# Navspark_NS-T_Adapter.net
KiCad netlist of a schematic drawn in EAGLE
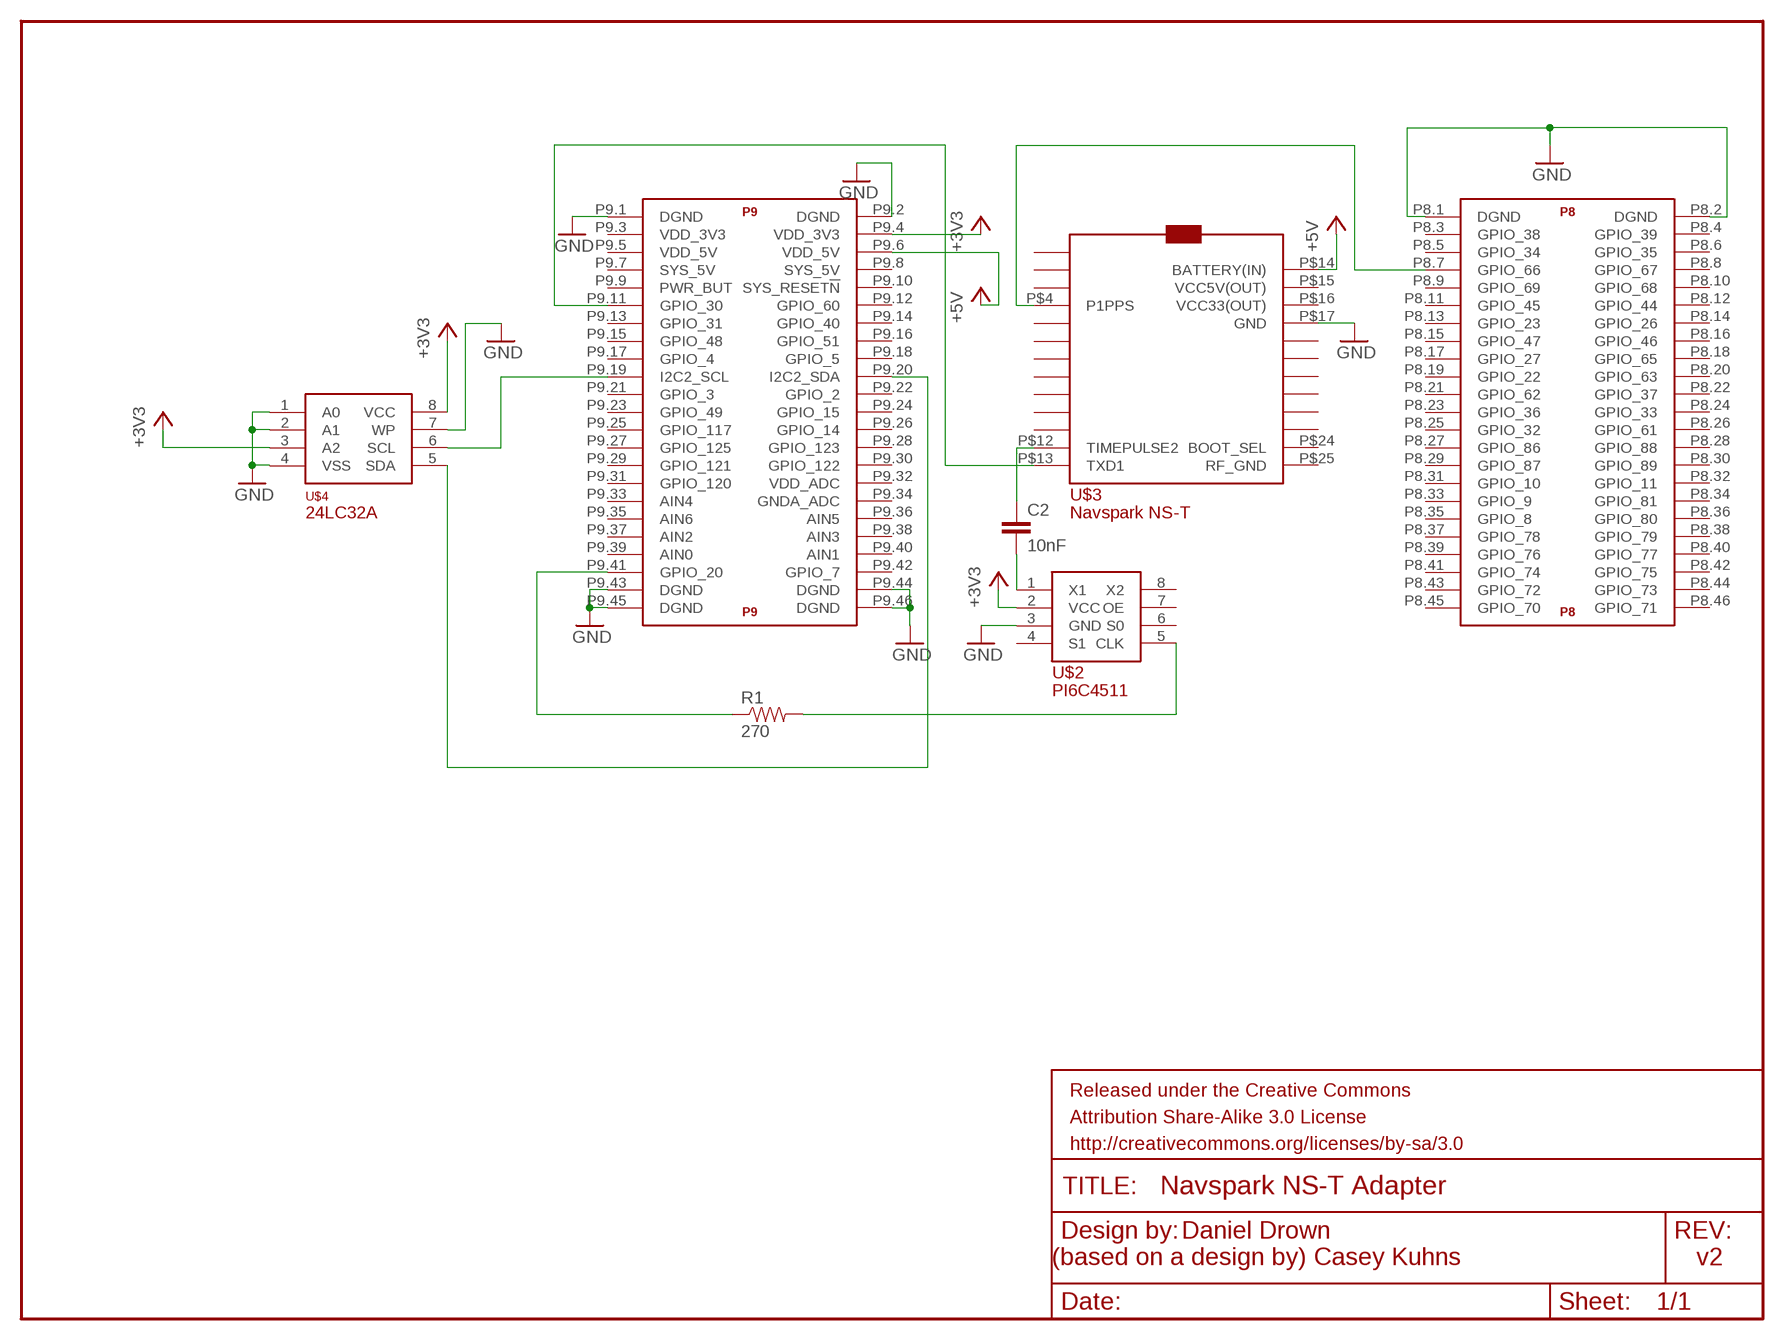
[diagram p0: schematic, sheet 1]

(export (version "E")
  (design (tool "Eeschema 10.0.6"))
  (components
    (comp (ref "C2")
      (value "10nF")
      (footprint "eagle-import:0805")
      (libsource (lib "eagle-import") (part "CAP0805"))
    )
    (comp (ref "FRAME1")
      (value "FRAME-LETTER")
      (footprint "eagle-import:CREATIVE_COMMONS")
      (libsource (lib "eagle-import") (part "FRAME-LETTER"))
    )
    (comp (ref "R1")
      (value "270")
      (footprint "eagle-import:0805")
      (libsource (lib "eagle-import") (part "RESISTOR0805-RES"))
    )
    (comp (ref "U$1")
      (value "BEAGLE_BONE_BLACK_CAPE")
      (footprint "eagle-import:BEAGLE_BONE_BLACK_CAPE")
      (libsource (lib "eagle-import") (part "BEAGLE_BONE_BLACK_CAPE"))
    )
    (comp (ref "U$2")
      (value "PI6C4511WE")
      (footprint "eagle-import:8-SOIC")
      (libsource (lib "eagle-import") (part "PI6C4511WE"))
    )
    (comp (ref "U$3")
      (value "NS-T")
      (footprint "eagle-import:BREADBOARD")
      (libsource (lib "eagle-import") (part "NS-T"))
    )
    (comp (ref "U$4")
      (value "24LC32A")
      (footprint "eagle-import:SOIC8")
      (libsource (lib "eagle-import") (part "24LC32A"))
    )
  )
  (nets
    (net (code "1") (name "+3V3") (class "Default")
      (node (ref "U$1") (pin "P9.4") (pinfunction "VDD_3V3_P9.4") (pintype "bidirectional"))
      (node (ref "U$2") (pin "2") (pinfunction "VCC_2") (pintype "bidirectional"))
      (node (ref "U$4") (pin "3") (pinfunction "A2_3") (pintype "bidirectional"))
      (node (ref "U$4") (pin "8") (pinfunction "VCC_8") (pintype "bidirectional"))
    )
    (net (code "2") (name "+5V") (class "Default")
      (node (ref "U$1") (pin "P9.6") (pinfunction "VDD_5V_P9.6") (pintype "bidirectional"))
      (node (ref "U$3") (pin "P$14") (pinfunction "BATTERY(IN)_P$14") (pintype "power_in"))
    )
    (net (code "3") (name "GND") (class "Default")
      (node (ref "U$1") (pin "P8.1") (pinfunction "DGND_P8.1") (pintype "bidirectional"))
      (node (ref "U$1") (pin "P8.2") (pinfunction "DGND_P8.2") (pintype "bidirectional"))
      (node (ref "U$1") (pin "P9.1") (pinfunction "DGND_P9.1") (pintype "bidirectional"))
      (node (ref "U$1") (pin "P9.2") (pinfunction "DGND_P9.2") (pintype "bidirectional"))
      (node (ref "U$1") (pin "P9.43") (pinfunction "DGND_P9.43") (pintype "bidirectional"))
      (node (ref "U$1") (pin "P9.44") (pinfunction "DGND_P9.44") (pintype "bidirectional"))
      (node (ref "U$1") (pin "P9.45") (pinfunction "DGND_P9.45") (pintype "bidirectional"))
      (node (ref "U$1") (pin "P9.46") (pinfunction "DGND_P9.46") (pintype "bidirectional"))
      (node (ref "U$2") (pin "3") (pinfunction "GND_3") (pintype "bidirectional"))
      (node (ref "U$3") (pin "P$17") (pinfunction "GND_P$17") (pintype "bidirectional"))
      (node (ref "U$4") (pin "1") (pinfunction "A0_1") (pintype "bidirectional"))
      (node (ref "U$4") (pin "2") (pinfunction "A1_2") (pintype "bidirectional"))
      (node (ref "U$4") (pin "4") (pinfunction "VSS_4") (pintype "bidirectional"))
      (node (ref "U$4") (pin "7") (pinfunction "WP_7") (pintype "bidirectional"))
    )
    (net (code "4") (name "Net-(U$1A-GPIO_66)") (class "Default")
      (node (ref "U$1") (pin "P8.7") (pinfunction "GPIO_66_P8.7") (pintype "bidirectional"))
      (node (ref "U$3") (pin "P$4") (pinfunction "P1PPS_P$4") (pintype "output"))
    )
    (net (code "5") (name "Net-(U$1B-GPIO_20)") (class "Default")
      (node (ref "R1") (pin "1") (pinfunction "1_1") (pintype "passive"))
      (node (ref "U$1") (pin "P9.41") (pinfunction "GPIO_20_P9.41") (pintype "bidirectional"))
    )
    (net (code "6") (name "Net-(U$1B-GPIO_30)") (class "Default")
      (node (ref "U$1") (pin "P9.11") (pinfunction "GPIO_30_P9.11") (pintype "bidirectional"))
      (node (ref "U$3") (pin "P$13") (pinfunction "TXD1_P$13") (pintype "output"))
    )
    (net (code "7") (name "Net-(U$1B-I2C2_SCL)") (class "Default")
      (node (ref "U$1") (pin "P9.19") (pinfunction "I2C2_SCL_P9.19") (pintype "bidirectional"))
      (node (ref "U$4") (pin "6") (pinfunction "SCL_6") (pintype "bidirectional"))
    )
    (net (code "8") (name "Net-(U$1B-I2C2_SDA)") (class "Default")
      (node (ref "U$1") (pin "P9.20") (pinfunction "I2C2_SDA_P9.20") (pintype "bidirectional"))
      (node (ref "U$4") (pin "5") (pinfunction "SDA_5") (pintype "bidirectional"))
    )
    (net (code "9") (name "Net-(U$2-CLK)") (class "Default")
      (node (ref "R1") (pin "2") (pinfunction "2_2") (pintype "passive"))
      (node (ref "U$2") (pin "5") (pinfunction "CLK_5") (pintype "bidirectional"))
    )
    (net (code "10") (name "Net-(U$2-X1)") (class "Default")
      (node (ref "C2") (pin "2") (pinfunction "2_2") (pintype "passive"))
      (node (ref "U$2") (pin "1") (pinfunction "X1_1") (pintype "bidirectional"))
    )
    (net (code "11") (name "Net-(U$3-TIMEPULSE2)") (class "Default")
      (node (ref "C2") (pin "1") (pinfunction "1_1") (pintype "passive"))
      (node (ref "U$3") (pin "P$12") (pinfunction "TIMEPULSE2_P$12") (pintype "output"))
    )
    (net (code "12") (name "unconnected-(U$1A-GPIO_8-PadP8.35)") (class "Default")
      (node (ref "U$1") (pin "P8.35") (pinfunction "GPIO_8_P8.35") (pintype "bidirectional"))
    )
    (net (code "13") (name "unconnected-(U$1A-GPIO_9-PadP8.33)") (class "Default")
      (node (ref "U$1") (pin "P8.33") (pinfunction "GPIO_9_P8.33") (pintype "bidirectional"))
    )
    (net (code "14") (name "unconnected-(U$1A-GPIO_10-PadP8.31)") (class "Default")
      (node (ref "U$1") (pin "P8.31") (pinfunction "GPIO_10_P8.31") (pintype "bidirectional"))
    )
    (net (code "15") (name "unconnected-(U$1A-GPIO_11-PadP8.32)") (class "Default")
      (node (ref "U$1") (pin "P8.32") (pinfunction "GPIO_11_P8.32") (pintype "bidirectional"))
    )
    (net (code "16") (name "unconnected-(U$1A-GPIO_22-PadP8.19)") (class "Default")
      (node (ref "U$1") (pin "P8.19") (pinfunction "GPIO_22_P8.19") (pintype "bidirectional"))
    )
    (net (code "17") (name "unconnected-(U$1A-GPIO_23-PadP8.13)") (class "Default")
      (node (ref "U$1") (pin "P8.13") (pinfunction "GPIO_23_P8.13") (pintype "bidirectional"))
    )
    (net (code "18") (name "unconnected-(U$1A-GPIO_26-PadP8.14)") (class "Default")
      (node (ref "U$1") (pin "P8.14") (pinfunction "GPIO_26_P8.14") (pintype "bidirectional"))
    )
    (net (code "19") (name "unconnected-(U$1A-GPIO_27-PadP8.17)") (class "Default")
      (node (ref "U$1") (pin "P8.17") (pinfunction "GPIO_27_P8.17") (pintype "bidirectional"))
    )
    (net (code "20") (name "unconnected-(U$1A-GPIO_32-PadP8.25)") (class "Default")
      (node (ref "U$1") (pin "P8.25") (pinfunction "GPIO_32_P8.25") (pintype "bidirectional"))
    )
    (net (code "21") (name "unconnected-(U$1A-GPIO_33-PadP8.24)") (class "Default")
      (node (ref "U$1") (pin "P8.24") (pinfunction "GPIO_33_P8.24") (pintype "bidirectional"))
    )
    (net (code "22") (name "unconnected-(U$1A-GPIO_34-PadP8.5)") (class "Default")
      (node (ref "U$1") (pin "P8.5") (pinfunction "GPIO_34_P8.5") (pintype "bidirectional"))
    )
    (net (code "23") (name "unconnected-(U$1A-GPIO_35-PadP8.6)") (class "Default")
      (node (ref "U$1") (pin "P8.6") (pinfunction "GPIO_35_P8.6") (pintype "bidirectional"))
    )
    (net (code "24") (name "unconnected-(U$1A-GPIO_36-PadP8.23)") (class "Default")
      (node (ref "U$1") (pin "P8.23") (pinfunction "GPIO_36_P8.23") (pintype "bidirectional"))
    )
    (net (code "25") (name "unconnected-(U$1A-GPIO_37-PadP8.22)") (class "Default")
      (node (ref "U$1") (pin "P8.22") (pinfunction "GPIO_37_P8.22") (pintype "bidirectional"))
    )
    (net (code "26") (name "unconnected-(U$1A-GPIO_38-PadP8.3)") (class "Default")
      (node (ref "U$1") (pin "P8.3") (pinfunction "GPIO_38_P8.3") (pintype "bidirectional"))
    )
    (net (code "27") (name "unconnected-(U$1A-GPIO_39-PadP8.4)") (class "Default")
      (node (ref "U$1") (pin "P8.4") (pinfunction "GPIO_39_P8.4") (pintype "bidirectional"))
    )
    (net (code "28") (name "unconnected-(U$1A-GPIO_44-PadP8.12)") (class "Default")
      (node (ref "U$1") (pin "P8.12") (pinfunction "GPIO_44_P8.12") (pintype "bidirectional"))
    )
    (net (code "29") (name "unconnected-(U$1A-GPIO_45-PadP8.11)") (class "Default")
      (node (ref "U$1") (pin "P8.11") (pinfunction "GPIO_45_P8.11") (pintype "bidirectional"))
    )
    (net (code "30") (name "unconnected-(U$1A-GPIO_46-PadP8.16)") (class "Default")
      (node (ref "U$1") (pin "P8.16") (pinfunction "GPIO_46_P8.16") (pintype "bidirectional"))
    )
    (net (code "31") (name "unconnected-(U$1A-GPIO_47-PadP8.15)") (class "Default")
      (node (ref "U$1") (pin "P8.15") (pinfunction "GPIO_47_P8.15") (pintype "bidirectional"))
    )
    (net (code "32") (name "unconnected-(U$1A-GPIO_61-PadP8.26)") (class "Default")
      (node (ref "U$1") (pin "P8.26") (pinfunction "GPIO_61_P8.26") (pintype "bidirectional"))
    )
    (net (code "33") (name "unconnected-(U$1A-GPIO_62-PadP8.21)") (class "Default")
      (node (ref "U$1") (pin "P8.21") (pinfunction "GPIO_62_P8.21") (pintype "bidirectional"))
    )
    (net (code "34") (name "unconnected-(U$1A-GPIO_63-PadP8.20)") (class "Default")
      (node (ref "U$1") (pin "P8.20") (pinfunction "GPIO_63_P8.20") (pintype "bidirectional"))
    )
    (net (code "35") (name "unconnected-(U$1A-GPIO_65-PadP8.18)") (class "Default")
      (node (ref "U$1") (pin "P8.18") (pinfunction "GPIO_65_P8.18") (pintype "bidirectional"))
    )
    (net (code "36") (name "unconnected-(U$1A-GPIO_67-PadP8.8)") (class "Default")
      (node (ref "U$1") (pin "P8.8") (pinfunction "GPIO_67_P8.8") (pintype "bidirectional"))
    )
    (net (code "37") (name "unconnected-(U$1A-GPIO_68-PadP8.10)") (class "Default")
      (node (ref "U$1") (pin "P8.10") (pinfunction "GPIO_68_P8.10") (pintype "bidirectional"))
    )
    (net (code "38") (name "unconnected-(U$1A-GPIO_69-PadP8.9)") (class "Default")
      (node (ref "U$1") (pin "P8.9") (pinfunction "GPIO_69_P8.9") (pintype "bidirectional"))
    )
    (net (code "39") (name "unconnected-(U$1A-GPIO_70-PadP8.45)") (class "Default")
      (node (ref "U$1") (pin "P8.45") (pinfunction "GPIO_70_P8.45") (pintype "bidirectional"))
    )
    (net (code "40") (name "unconnected-(U$1A-GPIO_71-PadP8.46)") (class "Default")
      (node (ref "U$1") (pin "P8.46") (pinfunction "GPIO_71_P8.46") (pintype "bidirectional"))
    )
    (net (code "41") (name "unconnected-(U$1A-GPIO_72-PadP8.43)") (class "Default")
      (node (ref "U$1") (pin "P8.43") (pinfunction "GPIO_72_P8.43") (pintype "bidirectional"))
    )
    (net (code "42") (name "unconnected-(U$1A-GPIO_73-PadP8.44)") (class "Default")
      (node (ref "U$1") (pin "P8.44") (pinfunction "GPIO_73_P8.44") (pintype "bidirectional"))
    )
    (net (code "43") (name "unconnected-(U$1A-GPIO_74-PadP8.41)") (class "Default")
      (node (ref "U$1") (pin "P8.41") (pinfunction "GPIO_74_P8.41") (pintype "bidirectional"))
    )
    (net (code "44") (name "unconnected-(U$1A-GPIO_75-PadP8.42)") (class "Default")
      (node (ref "U$1") (pin "P8.42") (pinfunction "GPIO_75_P8.42") (pintype "bidirectional"))
    )
    (net (code "45") (name "unconnected-(U$1A-GPIO_76-PadP8.39)") (class "Default")
      (node (ref "U$1") (pin "P8.39") (pinfunction "GPIO_76_P8.39") (pintype "bidirectional"))
    )
    (net (code "46") (name "unconnected-(U$1A-GPIO_77-PadP8.40)") (class "Default")
      (node (ref "U$1") (pin "P8.40") (pinfunction "GPIO_77_P8.40") (pintype "bidirectional"))
    )
    (net (code "47") (name "unconnected-(U$1A-GPIO_78-PadP8.37)") (class "Default")
      (node (ref "U$1") (pin "P8.37") (pinfunction "GPIO_78_P8.37") (pintype "bidirectional"))
    )
    (net (code "48") (name "unconnected-(U$1A-GPIO_79-PadP8.38)") (class "Default")
      (node (ref "U$1") (pin "P8.38") (pinfunction "GPIO_79_P8.38") (pintype "bidirectional"))
    )
    (net (code "49") (name "unconnected-(U$1A-GPIO_80-PadP8.36)") (class "Default")
      (node (ref "U$1") (pin "P8.36") (pinfunction "GPIO_80_P8.36") (pintype "bidirectional"))
    )
    (net (code "50") (name "unconnected-(U$1A-GPIO_81-PadP8.34)") (class "Default")
      (node (ref "U$1") (pin "P8.34") (pinfunction "GPIO_81_P8.34") (pintype "bidirectional"))
    )
    (net (code "51") (name "unconnected-(U$1A-GPIO_86-PadP8.27)") (class "Default")
      (node (ref "U$1") (pin "P8.27") (pinfunction "GPIO_86_P8.27") (pintype "bidirectional"))
    )
    (net (code "52") (name "unconnected-(U$1A-GPIO_87-PadP8.29)") (class "Default")
      (node (ref "U$1") (pin "P8.29") (pinfunction "GPIO_87_P8.29") (pintype "bidirectional"))
    )
    (net (code "53") (name "unconnected-(U$1A-GPIO_88-PadP8.28)") (class "Default")
      (node (ref "U$1") (pin "P8.28") (pinfunction "GPIO_88_P8.28") (pintype "bidirectional"))
    )
    (net (code "54") (name "unconnected-(U$1A-GPIO_89-PadP8.30)") (class "Default")
      (node (ref "U$1") (pin "P8.30") (pinfunction "GPIO_89_P8.30") (pintype "bidirectional"))
    )
    (net (code "55") (name "unconnected-(U$1B-AIN0-PadP9.39)") (class "Default")
      (node (ref "U$1") (pin "P9.39") (pinfunction "AIN0_P9.39") (pintype "bidirectional"))
    )
    (net (code "56") (name "unconnected-(U$1B-AIN1-PadP9.40)") (class "Default")
      (node (ref "U$1") (pin "P9.40") (pinfunction "AIN1_P9.40") (pintype "bidirectional"))
    )
    (net (code "57") (name "unconnected-(U$1B-AIN2-PadP9.37)") (class "Default")
      (node (ref "U$1") (pin "P9.37") (pinfunction "AIN2_P9.37") (pintype "bidirectional"))
    )
    (net (code "58") (name "unconnected-(U$1B-AIN3-PadP9.38)") (class "Default")
      (node (ref "U$1") (pin "P9.38") (pinfunction "AIN3_P9.38") (pintype "bidirectional"))
    )
    (net (code "59") (name "unconnected-(U$1B-AIN4-PadP9.33)") (class "Default")
      (node (ref "U$1") (pin "P9.33") (pinfunction "AIN4_P9.33") (pintype "bidirectional"))
    )
    (net (code "60") (name "unconnected-(U$1B-AIN5-PadP9.36)") (class "Default")
      (node (ref "U$1") (pin "P9.36") (pinfunction "AIN5_P9.36") (pintype "bidirectional"))
    )
    (net (code "61") (name "unconnected-(U$1B-AIN6-PadP9.35)") (class "Default")
      (node (ref "U$1") (pin "P9.35") (pinfunction "AIN6_P9.35") (pintype "bidirectional"))
    )
    (net (code "62") (name "unconnected-(U$1B-GNDA_ADC-PadP9.34)") (class "Default")
      (node (ref "U$1") (pin "P9.34") (pinfunction "GNDA_ADC_P9.34") (pintype "bidirectional"))
    )
    (net (code "63") (name "unconnected-(U$1B-GPIO_2-PadP9.22)") (class "Default")
      (node (ref "U$1") (pin "P9.22") (pinfunction "GPIO_2_P9.22") (pintype "bidirectional"))
    )
    (net (code "64") (name "unconnected-(U$1B-GPIO_3-PadP9.21)") (class "Default")
      (node (ref "U$1") (pin "P9.21") (pinfunction "GPIO_3_P9.21") (pintype "bidirectional"))
    )
    (net (code "65") (name "unconnected-(U$1B-GPIO_4-PadP9.17)") (class "Default")
      (node (ref "U$1") (pin "P9.17") (pinfunction "GPIO_4_P9.17") (pintype "bidirectional"))
    )
    (net (code "66") (name "unconnected-(U$1B-GPIO_5-PadP9.18)") (class "Default")
      (node (ref "U$1") (pin "P9.18") (pinfunction "GPIO_5_P9.18") (pintype "bidirectional"))
    )
    (net (code "67") (name "unconnected-(U$1B-GPIO_7-PadP9.42)") (class "Default")
      (node (ref "U$1") (pin "P9.42") (pinfunction "GPIO_7_P9.42") (pintype "bidirectional"))
    )
    (net (code "68") (name "unconnected-(U$1B-GPIO_14-PadP9.26)") (class "Default")
      (node (ref "U$1") (pin "P9.26") (pinfunction "GPIO_14_P9.26") (pintype "bidirectional"))
    )
    (net (code "69") (name "unconnected-(U$1B-GPIO_15-PadP9.24)") (class "Default")
      (node (ref "U$1") (pin "P9.24") (pinfunction "GPIO_15_P9.24") (pintype "bidirectional"))
    )
    (net (code "70") (name "unconnected-(U$1B-GPIO_31-PadP9.13)") (class "Default")
      (node (ref "U$1") (pin "P9.13") (pinfunction "GPIO_31_P9.13") (pintype "bidirectional"))
    )
    (net (code "71") (name "unconnected-(U$1B-GPIO_40-PadP9.14)") (class "Default")
      (node (ref "U$1") (pin "P9.14") (pinfunction "GPIO_40_P9.14") (pintype "bidirectional"))
    )
    (net (code "72") (name "unconnected-(U$1B-GPIO_48-PadP9.15)") (class "Default")
      (node (ref "U$1") (pin "P9.15") (pinfunction "GPIO_48_P9.15") (pintype "bidirectional"))
    )
    (net (code "73") (name "unconnected-(U$1B-GPIO_49-PadP9.23)") (class "Default")
      (node (ref "U$1") (pin "P9.23") (pinfunction "GPIO_49_P9.23") (pintype "bidirectional"))
    )
    (net (code "74") (name "unconnected-(U$1B-GPIO_51-PadP9.16)") (class "Default")
      (node (ref "U$1") (pin "P9.16") (pinfunction "GPIO_51_P9.16") (pintype "bidirectional"))
    )
    (net (code "75") (name "unconnected-(U$1B-GPIO_60-PadP9.12)") (class "Default")
      (node (ref "U$1") (pin "P9.12") (pinfunction "GPIO_60_P9.12") (pintype "bidirectional"))
    )
    (net (code "76") (name "unconnected-(U$1B-GPIO_117-PadP9.25)") (class "Default")
      (node (ref "U$1") (pin "P9.25") (pinfunction "GPIO_117_P9.25") (pintype "bidirectional"))
    )
    (net (code "77") (name "unconnected-(U$1B-GPIO_120-PadP9.31)") (class "Default")
      (node (ref "U$1") (pin "P9.31") (pinfunction "GPIO_120_P9.31") (pintype "bidirectional"))
    )
    (net (code "78") (name "unconnected-(U$1B-GPIO_121-PadP9.29)") (class "Default")
      (node (ref "U$1") (pin "P9.29") (pinfunction "GPIO_121_P9.29") (pintype "bidirectional"))
    )
    (net (code "79") (name "unconnected-(U$1B-GPIO_122-PadP9.30)") (class "Default")
      (node (ref "U$1") (pin "P9.30") (pinfunction "GPIO_122_P9.30") (pintype "bidirectional"))
    )
    (net (code "80") (name "unconnected-(U$1B-GPIO_123-PadP9.28)") (class "Default")
      (node (ref "U$1") (pin "P9.28") (pinfunction "GPIO_123_P9.28") (pintype "bidirectional"))
    )
    (net (code "81") (name "unconnected-(U$1B-GPIO_125-PadP9.27)") (class "Default")
      (node (ref "U$1") (pin "P9.27") (pinfunction "GPIO_125_P9.27") (pintype "bidirectional"))
    )
    (net (code "82") (name "unconnected-(U$1B-PWR_BUT-PadP9.9)") (class "Default")
      (node (ref "U$1") (pin "P9.9") (pinfunction "PWR_BUT_P9.9") (pintype "bidirectional"))
    )
    (net (code "83") (name "unconnected-(U$1B-SYS_5V-PadP9.7)") (class "Default")
      (node (ref "U$1") (pin "P9.7") (pinfunction "SYS_5V_P9.7") (pintype "bidirectional"))
    )
    (net (code "84") (name "unconnected-(U$1B-SYS_5V-PadP9.8)") (class "Default")
      (node (ref "U$1") (pin "P9.8") (pinfunction "SYS_5V_P9.8") (pintype "bidirectional"))
    )
    (net (code "85") (name "unconnected-(U$1B-SYS_RESET~{N}-PadP9.10)") (class "Default")
      (node (ref "U$1") (pin "P9.10") (pinfunction "SYS_RESET~{N}_P9.10") (pintype "bidirectional"))
    )
    (net (code "86") (name "unconnected-(U$1B-VDD_3V3-PadP9.3)") (class "Default")
      (node (ref "U$1") (pin "P9.3") (pinfunction "VDD_3V3_P9.3") (pintype "bidirectional"))
    )
    (net (code "87") (name "unconnected-(U$1B-VDD_5V-PadP9.5)") (class "Default")
      (node (ref "U$1") (pin "P9.5") (pinfunction "VDD_5V_P9.5") (pintype "bidirectional"))
    )
    (net (code "88") (name "unconnected-(U$1B-VDD_ADC-PadP9.32)") (class "Default")
      (node (ref "U$1") (pin "P9.32") (pinfunction "VDD_ADC_P9.32") (pintype "bidirectional"))
    )
    (net (code "89") (name "unconnected-(U$2-OE-Pad7)") (class "Default")
      (node (ref "U$2") (pin "7") (pinfunction "OE_7") (pintype "bidirectional"))
    )
    (net (code "90") (name "unconnected-(U$2-S0-Pad6)") (class "Default")
      (node (ref "U$2") (pin "6") (pinfunction "S0_6") (pintype "bidirectional"))
    )
    (net (code "91") (name "unconnected-(U$2-S1-Pad4)") (class "Default")
      (node (ref "U$2") (pin "4") (pinfunction "S1_4") (pintype "bidirectional"))
    )
    (net (code "92") (name "unconnected-(U$2-X2-Pad8)") (class "Default")
      (node (ref "U$2") (pin "8") (pinfunction "X2_8") (pintype "bidirectional"))
    )
    (net (code "93") (name "unconnected-(U$3-BOOT_SEL-PadP$24)") (class "Default")
      (node (ref "U$3") (pin "P$24") (pinfunction "BOOT_SEL_P$24") (pintype "input"))
    )
    (net (code "94") (name "unconnected-(U$3-PadP$1)") (class "Default")
      (node (ref "U$3") (pin "P$1") (pinfunction "P$1_P$1") (pintype "no_connect"))
    )
    (net (code "95") (name "unconnected-(U$3-PadP$2)") (class "Default")
      (node (ref "U$3") (pin "P$2") (pinfunction "P$2_P$2") (pintype "no_connect"))
    )
    (net (code "96") (name "unconnected-(U$3-PadP$3)") (class "Default")
      (node (ref "U$3") (pin "P$3") (pinfunction "P$3_P$3") (pintype "no_connect"))
    )
    (net (code "97") (name "unconnected-(U$3-PadP$5)") (class "Default")
      (node (ref "U$3") (pin "P$5") (pinfunction "P$5_P$5") (pintype "no_connect"))
    )
    (net (code "98") (name "unconnected-(U$3-PadP$6)") (class "Default")
      (node (ref "U$3") (pin "P$6") (pinfunction "P$6_P$6") (pintype "no_connect"))
    )
    (net (code "99") (name "unconnected-(U$3-PadP$7)") (class "Default")
      (node (ref "U$3") (pin "P$7") (pinfunction "P$7_P$7") (pintype "no_connect"))
    )
    (net (code "100") (name "unconnected-(U$3-PadP$8)") (class "Default")
      (node (ref "U$3") (pin "P$8") (pinfunction "P$8_P$8") (pintype "no_connect"))
    )
    (net (code "101") (name "unconnected-(U$3-PadP$9)") (class "Default")
      (node (ref "U$3") (pin "P$9") (pinfunction "P$9_P$9") (pintype "no_connect"))
    )
    (net (code "102") (name "unconnected-(U$3-PadP$10)") (class "Default")
      (node (ref "U$3") (pin "P$10") (pinfunction "P$10_P$10") (pintype "no_connect"))
    )
    (net (code "103") (name "unconnected-(U$3-PadP$11)") (class "Default")
      (node (ref "U$3") (pin "P$11") (pinfunction "P$11_P$11") (pintype "no_connect"))
    )
    (net (code "104") (name "unconnected-(U$3-PadP$18)") (class "Default")
      (node (ref "U$3") (pin "P$18") (pinfunction "P$18_P$18") (pintype "no_connect"))
    )
    (net (code "105") (name "unconnected-(U$3-PadP$19)") (class "Default")
      (node (ref "U$3") (pin "P$19") (pinfunction "P$19_P$19") (pintype "no_connect"))
    )
    (net (code "106") (name "unconnected-(U$3-PadP$20)") (class "Default")
      (node (ref "U$3") (pin "P$20") (pinfunction "P$20_P$20") (pintype "no_connect"))
    )
    (net (code "107") (name "unconnected-(U$3-PadP$21)") (class "Default")
      (node (ref "U$3") (pin "P$21") (pinfunction "P$21_P$21") (pintype "no_connect"))
    )
    (net (code "108") (name "unconnected-(U$3-PadP$22)") (class "Default")
      (node (ref "U$3") (pin "P$22") (pinfunction "P$22_P$22") (pintype "no_connect"))
    )
    (net (code "109") (name "unconnected-(U$3-PadP$23)") (class "Default")
      (node (ref "U$3") (pin "P$23") (pinfunction "P$23_P$23") (pintype "no_connect"))
    )
    (net (code "110") (name "unconnected-(U$3-RF_GND-PadP$25)") (class "Default")
      (node (ref "U$3") (pin "P$25") (pinfunction "RF_GND_P$25") (pintype "bidirectional"))
    )
    (net (code "111") (name "unconnected-(U$3-VCC5V(OUT)-PadP$15)") (class "Default")
      (node (ref "U$3") (pin "P$15") (pinfunction "VCC5V(OUT)_P$15") (pintype "output"))
    )
    (net (code "112") (name "unconnected-(U$3-VCC33(OUT)-PadP$16)") (class "Default")
      (node (ref "U$3") (pin "P$16") (pinfunction "VCC33(OUT)_P$16") (pintype "output"))
    )
  )
)
